# SFP.net
KiCad netlist of a schematic drawn in Altium Designer
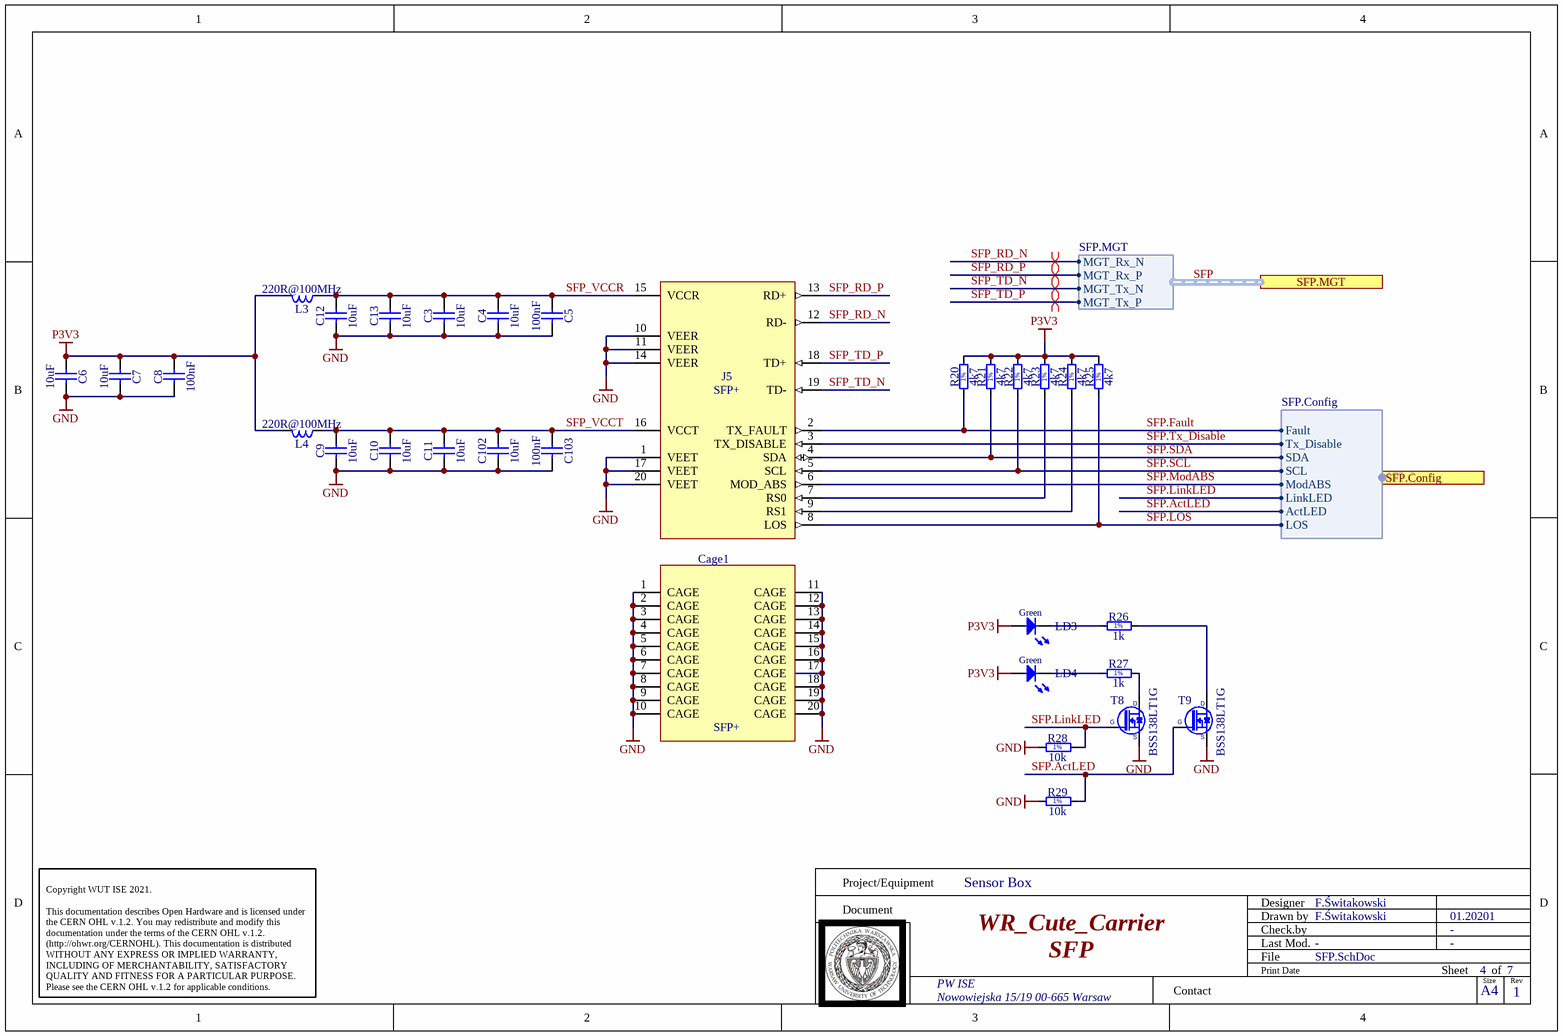
[diagram p0: SFP.SchDoc]

(export (version "E")
  (design (tool "Eeschema 10.0.6"))
  (components
    (comp (ref "C3")
      (value "10uF")
      (footprint "CAPC1005X70N")
      (description "Non-polarised capacitor")
      (fields
        (field (name "PART NUMBER") "CC0402_10UF_6.3V_20%_X5R")
        (field (name "VOLTAGE") "6.3V")
        (field (name "AUTHOR") "CERN DEM JLC")
      )
      (libsource (lib "Capacitors") (part "Capacitor - non polarized"))
    )
    (comp (ref "C4")
      (value "10uF")
      (footprint "CAPC1005X70N")
      (description "Non-polarised capacitor")
      (fields
        (field (name "PART NUMBER") "CC0402_10UF_6.3V_20%_X5R")
        (field (name "VOLTAGE") "6.3V")
        (field (name "AUTHOR") "CERN DEM JLC")
      )
      (libsource (lib "Capacitors") (part "Capacitor - non polarized"))
    )
    (comp (ref "C5")
      (value "100nF")
      (footprint "CAPC1005X55N")
      (description "Non-polarised capacitor")
      (fields
        (field (name "PART NUMBER") "CC0402_100NF_25V_10%_X7R_YUDEN_TMK105B7104KVHF")
        (field (name "VOLTAGE") "25V")
        (field (name "AUTHOR") "CERN DEM JLC")
      )
      (libsource (lib "Capacitors") (part "Capacitor - non polarized"))
    )
    (comp (ref "C6")
      (value "10uF")
      (footprint "CAPC1005X70N")
      (description "Non-polarised capacitor")
      (fields
        (field (name "PART NUMBER") "CC0402_10UF_6.3V_20%_X5R")
        (field (name "VOLTAGE") "6.3V")
        (field (name "AUTHOR") "CERN DEM JLC")
      )
      (libsource (lib "Capacitors") (part "Capacitor - non polarized"))
    )
    (comp (ref "C7")
      (value "10uF")
      (footprint "CAPC1005X70N")
      (description "Non-polarised capacitor")
      (fields
        (field (name "PART NUMBER") "CC0402_10UF_6.3V_20%_X5R")
        (field (name "VOLTAGE") "6.3V")
        (field (name "AUTHOR") "CERN DEM JLC")
      )
      (libsource (lib "Capacitors") (part "Capacitor - non polarized"))
    )
    (comp (ref "C8")
      (value "100nF")
      (footprint "CAPC1005X55N")
      (description "Non-polarised capacitor")
      (fields
        (field (name "PART NUMBER") "CC0402_100NF_25V_10%_X7R_YUDEN_TMK105B7104KVHF")
        (field (name "VOLTAGE") "25V")
        (field (name "AUTHOR") "CERN DEM JLC")
      )
      (libsource (lib "Capacitors") (part "Capacitor - non polarized"))
    )
    (comp (ref "C9")
      (value "10uF")
      (footprint "CAPC1005X70N")
      (description "Non-polarised capacitor")
      (fields
        (field (name "PART NUMBER") "CC0402_10UF_6.3V_20%_X5R")
        (field (name "VOLTAGE") "6.3V")
        (field (name "AUTHOR") "CERN DEM JLC")
      )
      (libsource (lib "Capacitors") (part "Capacitor - non polarized"))
    )
    (comp (ref "C10")
      (value "10uF")
      (footprint "CAPC1005X70N")
      (description "Non-polarised capacitor")
      (fields
        (field (name "PART NUMBER") "CC0402_10UF_6.3V_20%_X5R")
        (field (name "VOLTAGE") "6.3V")
        (field (name "AUTHOR") "CERN DEM JLC")
      )
      (libsource (lib "Capacitors") (part "Capacitor - non polarized"))
    )
    (comp (ref "C11")
      (value "10uF")
      (footprint "CAPC1005X70N")
      (description "Non-polarised capacitor")
      (fields
        (field (name "PART NUMBER") "CC0402_10UF_6.3V_20%_X5R")
        (field (name "VOLTAGE") "6.3V")
        (field (name "AUTHOR") "CERN DEM JLC")
      )
      (libsource (lib "Capacitors") (part "Capacitor - non polarized"))
    )
    (comp (ref "C12")
      (value "10uF")
      (footprint "CAPC1005X70N")
      (description "Non-polarised capacitor")
      (fields
        (field (name "PART NUMBER") "CC0402_10UF_6.3V_20%_X5R")
        (field (name "VOLTAGE") "6.3V")
        (field (name "AUTHOR") "CERN DEM JLC")
      )
      (libsource (lib "Capacitors") (part "Capacitor - non polarized"))
    )
    (comp (ref "C13")
      (value "10uF")
      (footprint "CAPC1005X70N")
      (description "Non-polarised capacitor")
      (fields
        (field (name "PART NUMBER") "CC0402_10UF_6.3V_20%_X5R")
        (field (name "VOLTAGE") "6.3V")
        (field (name "AUTHOR") "CERN DEM JLC")
      )
      (libsource (lib "Capacitors") (part "Capacitor - non polarized"))
    )
    (comp (ref "C102")
      (value "10uF")
      (footprint "CAPC1005X70N")
      (description "Non-polarised capacitor")
      (fields
        (field (name "PART NUMBER") "CC0402_10UF_6.3V_20%_X5R")
        (field (name "VOLTAGE") "6.3V")
        (field (name "AUTHOR") "CERN DEM JLC")
      )
      (libsource (lib "Capacitors") (part "Capacitor - non polarized"))
    )
    (comp (ref "C103")
      (value "100nF")
      (footprint "CAPC1005X55N")
      (description "Non-polarised capacitor")
      (fields
        (field (name "PART NUMBER") "CC0402_100NF_25V_10%_X7R_YUDEN_TMK105B7104KVHF")
        (field (name "VOLTAGE") "25V")
        (field (name "AUTHOR") "CERN DEM JLC")
      )
      (libsource (lib "Capacitors") (part "Capacitor - non polarized"))
    )
    (comp (ref "Cage1")
      (value "SFP+")
      (footprint "TYCO_2007198-1")
      (description "SFP+ 1x1 Cage (20Pins)")
      (fields
        (field (name "PART NUMBER") "TYCO_2007198-1")
        (field (name "MANUFACTURER") "TYCO ELECTRONICS")
        (field (name "AUTHOR") "CERN DEM JLC")
      )
      (libsource (lib "Connectors") (part "SFP+ 1x1 Cage (20Pins)"))
    )
    (comp (ref "J5")
      (value "SFP+")
      (footprint "TYCO_1888247-1")
      (description "20 Position SFP+ Connector (Small Form-factor Pluggable)")
      (fields
        (field (name "PART NUMBER") "TYCO_1888247-1")
        (field (name "MANUFACTURER") "TYCO ELECTRONICS")
        (field (name "AUTHOR") "CERN DEM JLC")
      )
      (libsource (lib "Connectors") (part "SFP+x1"))
    )
    (comp (ref "L3")
      (value "220R@100MHz")
      (footprint "INDC2012X105N")
      (description "Inductor")
      (fields
        (field (name "PART NUMBER") "IND0805_MURATA_BLM21PG221SN1D")
        (field (name "POWER") "2A")
        (field (name "AUTHOR") "CERN DEM JLC")
      )
      (libsource (lib "Inductors & Transformers") (part "Inductor"))
    )
    (comp (ref "L4")
      (value "220R@100MHz")
      (footprint "INDC2012X105N")
      (description "Inductor")
      (fields
        (field (name "PART NUMBER") "IND0805_MURATA_BLM21PG221SN1D")
        (field (name "POWER") "2A")
        (field (name "AUTHOR") "CERN DEM JLC")
      )
      (libsource (lib "Inductors & Transformers") (part "Inductor"))
    )
    (comp (ref "LD3")
      (value "Green")
      (footprint "LED_AVAGO_HSME-C120")
      (description "LED Green 1C 2A")
      (fields
        (field (name "PART NUMBER") "LED_AVAGO_HSME-C120")
        (field (name "MANUFACTURER") "AVAGO TECHNOLOGIES")
        (field (name "AUTHOR") "CERN DEM JMW")
      )
      (libsource (lib "ICs And Semiconductors") (part "LED Green 1C 2A"))
    )
    (comp (ref "LD4")
      (value "Green")
      (footprint "LED_AVAGO_HSME-C120")
      (description "LED Green 1C 2A")
      (fields
        (field (name "PART NUMBER") "LED_AVAGO_HSME-C120")
        (field (name "MANUFACTURER") "AVAGO TECHNOLOGIES")
        (field (name "AUTHOR") "CERN DEM JMW")
      )
      (libsource (lib "ICs And Semiconductors") (part "LED Green 1C 2A"))
    )
    (comp (ref "R20")
      (value "4k7")
      (footprint "RESC1005X40N")
      (description "Resistor - 1%")
      (fields
        (field (name "PART NUMBER") "R0402_4K7_1%_0.0625W_100PPM")
        (field (name "MANUFACTURER") "GENERIC")
        (field (name "AUTHOR") "CERN DEM JLC")
      )
      (libsource (lib "Resistors") (part "Resistor - 1%"))
    )
    (comp (ref "R21")
      (value "4k7")
      (footprint "RESC1005X40N")
      (description "Resistor - 1%")
      (fields
        (field (name "PART NUMBER") "R0402_4K7_1%_0.0625W_100PPM")
        (field (name "MANUFACTURER") "GENERIC")
        (field (name "AUTHOR") "CERN DEM JLC")
      )
      (libsource (lib "Resistors") (part "Resistor - 1%"))
    )
    (comp (ref "R22")
      (value "4k7")
      (footprint "RESC1005X40N")
      (description "Resistor - 1%")
      (fields
        (field (name "PART NUMBER") "R0402_4K7_1%_0.0625W_100PPM")
        (field (name "MANUFACTURER") "GENERIC")
        (field (name "AUTHOR") "CERN DEM JLC")
      )
      (libsource (lib "Resistors") (part "Resistor - 1%"))
    )
    (comp (ref "R23")
      (value "4k7")
      (footprint "RESC1005X40N")
      (description "Resistor - 1%")
      (fields
        (field (name "PART NUMBER") "R0402_4K7_1%_0.0625W_100PPM")
        (field (name "MANUFACTURER") "GENERIC")
        (field (name "AUTHOR") "CERN DEM JLC")
      )
      (libsource (lib "Resistors") (part "Resistor - 1%"))
    )
    (comp (ref "R24")
      (value "4k7")
      (footprint "RESC1005X40N")
      (description "Resistor - 1%")
      (fields
        (field (name "PART NUMBER") "R0402_4K7_1%_0.0625W_100PPM")
        (field (name "MANUFACTURER") "GENERIC")
        (field (name "AUTHOR") "CERN DEM JLC")
      )
      (libsource (lib "Resistors") (part "Resistor - 1%"))
    )
    (comp (ref "R25")
      (value "4k7")
      (footprint "RESC1005X40N")
      (description "Resistor - 1%")
      (fields
        (field (name "PART NUMBER") "R0402_4K7_1%_0.0625W_100PPM")
        (field (name "MANUFACTURER") "GENERIC")
        (field (name "AUTHOR") "CERN DEM JLC")
      )
      (libsource (lib "Resistors") (part "Resistor - 1%"))
    )
    (comp (ref "R26")
      (value "1k")
      (footprint "RESC1005X40N")
      (description "Resistor - 1%")
      (fields
        (field (name "PART NUMBER") "R0402_1K_1%_0.0625W_100PPM")
        (field (name "POWER") "0.0625W")
        (field (name "AUTHOR") "CERN DEM JLC")
      )
      (libsource (lib "Resistors") (part "Resistor - 1%"))
    )
    (comp (ref "R27")
      (value "1k")
      (footprint "RESC1005X40N")
      (description "Resistor - 1%")
      (fields
        (field (name "PART NUMBER") "R0402_1K_1%_0.0625W_100PPM")
        (field (name "POWER") "0.0625W")
        (field (name "AUTHOR") "CERN DEM JLC")
      )
      (libsource (lib "Resistors") (part "Resistor - 1%"))
    )
    (comp (ref "R28")
      (value "10k")
      (footprint "RESC1608X55N")
      (description "Resistor - 1%")
      (fields
        (field (name "PART NUMBER") "R0603_10K_1%_0.1W_100PPM")
        (field (name "POWER") "0.1W")
        (field (name "AUTHOR") "CERN DEM JLC")
      )
      (libsource (lib "Resistors") (part "Resistor - 1%"))
    )
    (comp (ref "R29")
      (value "10k")
      (footprint "RESC1608X55N")
      (description "Resistor - 1%")
      (fields
        (field (name "PART NUMBER") "R0603_10K_1%_0.1W_100PPM")
        (field (name "POWER") "0.1W")
        (field (name "AUTHOR") "CERN DEM JLC")
      )
      (libsource (lib "Resistors") (part "Resistor - 1%"))
    )
    (comp (ref "T8")
      (value "BSS138LT1G")
      (footprint "SOT95P240X110-3N")
      (description "N-CHANNEL MOSFET WITH DIODE")
      (fields (field (name "MANUFACTURER") "ON SEMICONDUCTOR") (field (name "AUTHOR") "CERN DEM JLC"))
      (libsource (lib "ICs And Semiconductors") (part "N-MOSFET-D 1G 2S 3D"))
    )
    (comp (ref "T9")
      (value "BSS138LT1G")
      (footprint "SOT95P240X110-3N")
      (description "N-CHANNEL MOSFET WITH DIODE")
      (fields (field (name "MANUFACTURER") "ON SEMICONDUCTOR") (field (name "AUTHOR") "CERN DEM JLC"))
      (libsource (lib "ICs And Semiconductors") (part "N-MOSFET-D 1G 2S 3D"))
    )
  )
  (nets
    (net (code "3") (name "/SFP.ActLED") (class "Default")
      (node (ref "R29") (pin "2") (pinfunction "2_2") (pintype "passive"))
      (node (ref "T9") (pin "1") (pinfunction "G_1") (pintype "passive"))
    )
    (net (code "4") (name "/SFP.Fault") (class "Default")
      (node (ref "J5") (pin "2") (pinfunction "TX_FAULT_2") (pintype "output"))
      (node (ref "R20") (pin "1") (pinfunction "1_1") (pintype "passive"))
    )
    (net (code "5") (name "/SFP.LOS") (class "Default")
      (node (ref "J5") (pin "8") (pinfunction "LOS_8") (pintype "output"))
      (node (ref "R25") (pin "1") (pinfunction "1_1") (pintype "passive"))
    )
    (net (code "6") (name "/SFP.LinkLED") (class "Default")
      (node (ref "R28") (pin "2") (pinfunction "2_2") (pintype "passive"))
      (node (ref "T8") (pin "1") (pinfunction "G_1") (pintype "passive"))
    )
    (net (code "7") (name "/SFP.ModABS") (class "Default")
      (node (ref "J5") (pin "6") (pinfunction "MOD_ABS_6") (pintype "output"))
    )
    (net (code "8") (name "/SFP.SCL") (class "Default")
      (node (ref "J5") (pin "5") (pinfunction "SCL_5") (pintype "input"))
      (node (ref "R22") (pin "1") (pinfunction "1_1") (pintype "passive"))
    )
    (net (code "9") (name "/SFP.SDA") (class "Default")
      (node (ref "J5") (pin "4") (pinfunction "SDA_4") (pintype "bidirectional"))
      (node (ref "R21") (pin "1") (pinfunction "1_1") (pintype "passive"))
    )
    (net (code "10") (name "/SFP.Tx_Disable") (class "Default")
      (node (ref "J5") (pin "3") (pinfunction "TX_DISABLE_3") (pintype "input"))
    )
    (net (code "11") (name "/SFP_RD_N") (class "Default")
      (node (ref "J5") (pin "12") (pinfunction "RD-_12") (pintype "output"))
    )
    (net (code "12") (name "/SFP_RD_P") (class "Default")
      (node (ref "J5") (pin "13") (pinfunction "RD+_13") (pintype "output"))
    )
    (net (code "13") (name "/SFP_TD_N") (class "Default")
      (node (ref "J5") (pin "19") (pinfunction "TD-_19") (pintype "input"))
    )
    (net (code "14") (name "/SFP_TD_P") (class "Default")
      (node (ref "J5") (pin "18") (pinfunction "TD+_18") (pintype "input"))
    )
    (net (code "15") (name "/SFP_VCCR") (class "Default")
      (node (ref "C12") (pin "2") (pinfunction "2_2") (pintype "passive"))
      (node (ref "C13") (pin "2") (pinfunction "2_2") (pintype "passive"))
      (node (ref "C3") (pin "2") (pinfunction "2_2") (pintype "passive"))
      (node (ref "C4") (pin "2") (pinfunction "2_2") (pintype "passive"))
      (node (ref "C5") (pin "1") (pinfunction "1_1") (pintype "passive"))
      (node (ref "J5") (pin "15") (pinfunction "VCCR_15") (pintype "power_in"))
      (node (ref "L3") (pin "1") (pinfunction "1_1") (pintype "passive"))
    )
    (net (code "16") (name "/SFP_VCCT") (class "Default")
      (node (ref "C10") (pin "2") (pinfunction "2_2") (pintype "passive"))
      (node (ref "C102") (pin "2") (pinfunction "2_2") (pintype "passive"))
      (node (ref "C103") (pin "1") (pinfunction "1_1") (pintype "passive"))
      (node (ref "C11") (pin "2") (pinfunction "2_2") (pintype "passive"))
      (node (ref "C9") (pin "2") (pinfunction "2_2") (pintype "passive"))
      (node (ref "J5") (pin "16") (pinfunction "VCCT_16") (pintype "power_in"))
      (node (ref "L4") (pin "1") (pinfunction "1_1") (pintype "passive"))
    )
    (net (code "19") (name "GND") (class "Default")
      (node (ref "C10") (pin "1") (pinfunction "1_1") (pintype "passive"))
      (node (ref "C102") (pin "1") (pinfunction "1_1") (pintype "passive"))
      (node (ref "C103") (pin "2") (pinfunction "2_2") (pintype "passive"))
      (node (ref "C11") (pin "1") (pinfunction "1_1") (pintype "passive"))
      (node (ref "C12") (pin "1") (pinfunction "1_1") (pintype "passive"))
      (node (ref "C13") (pin "1") (pinfunction "1_1") (pintype "passive"))
      (node (ref "C3") (pin "1") (pinfunction "1_1") (pintype "passive"))
      (node (ref "C4") (pin "1") (pinfunction "1_1") (pintype "passive"))
      (node (ref "C5") (pin "2") (pinfunction "2_2") (pintype "passive"))
      (node (ref "C6") (pin "1") (pinfunction "1_1") (pintype "passive"))
      (node (ref "C7") (pin "1") (pinfunction "1_1") (pintype "passive"))
      (node (ref "C8") (pin "2") (pinfunction "2_2") (pintype "passive"))
      (node (ref "C9") (pin "1") (pinfunction "1_1") (pintype "passive"))
      (node (ref "Cage1") (pin "1") (pinfunction "CAGE_1") (pintype "power_in"))
      (node (ref "Cage1") (pin "10") (pinfunction "CAGE_10") (pintype "power_in"))
      (node (ref "Cage1") (pin "11") (pinfunction "CAGE_11") (pintype "power_in"))
      (node (ref "Cage1") (pin "12") (pinfunction "CAGE_12") (pintype "power_in"))
      (node (ref "Cage1") (pin "13") (pinfunction "CAGE_13") (pintype "power_in"))
      (node (ref "Cage1") (pin "14") (pinfunction "CAGE_14") (pintype "power_in"))
      (node (ref "Cage1") (pin "15") (pinfunction "CAGE_15") (pintype "power_in"))
      (node (ref "Cage1") (pin "16") (pinfunction "CAGE_16") (pintype "power_in"))
      (node (ref "Cage1") (pin "17") (pinfunction "CAGE_17") (pintype "power_in"))
      (node (ref "Cage1") (pin "18") (pinfunction "CAGE_18") (pintype "power_in"))
      (node (ref "Cage1") (pin "19") (pinfunction "CAGE_19") (pintype "power_in"))
      (node (ref "Cage1") (pin "2") (pinfunction "CAGE_2") (pintype "power_in"))
      (node (ref "Cage1") (pin "20") (pinfunction "CAGE_20") (pintype "power_in"))
      (node (ref "Cage1") (pin "3") (pinfunction "CAGE_3") (pintype "power_in"))
      (node (ref "Cage1") (pin "4") (pinfunction "CAGE_4") (pintype "power_in"))
      (node (ref "Cage1") (pin "5") (pinfunction "CAGE_5") (pintype "power_in"))
      (node (ref "Cage1") (pin "6") (pinfunction "CAGE_6") (pintype "power_in"))
      (node (ref "Cage1") (pin "7") (pinfunction "CAGE_7") (pintype "power_in"))
      (node (ref "Cage1") (pin "8") (pinfunction "CAGE_8") (pintype "power_in"))
      (node (ref "Cage1") (pin "9") (pinfunction "CAGE_9") (pintype "power_in"))
      (node (ref "J5") (pin "1") (pinfunction "VEET_1") (pintype "power_in"))
      (node (ref "J5") (pin "10") (pinfunction "VEER_10") (pintype "power_in"))
      (node (ref "J5") (pin "11") (pinfunction "VEER_11") (pintype "power_in"))
      (node (ref "J5") (pin "14") (pinfunction "VEER_14") (pintype "power_in"))
      (node (ref "J5") (pin "17") (pinfunction "VEET_17") (pintype "power_in"))
      (node (ref "J5") (pin "20") (pinfunction "VEET_20") (pintype "power_in"))
      (node (ref "R28") (pin "1") (pinfunction "1_1") (pintype "passive"))
      (node (ref "R29") (pin "1") (pinfunction "1_1") (pintype "passive"))
      (node (ref "T8") (pin "2") (pinfunction "S_2") (pintype "passive"))
      (node (ref "T9") (pin "2") (pinfunction "S_2") (pintype "passive"))
    )
    (net (code "20") (name "Net-(J5-RS0)") (class "Default")
      (node (ref "J5") (pin "7") (pinfunction "RS0_7") (pintype "input"))
      (node (ref "R23") (pin "1") (pinfunction "1_1") (pintype "passive"))
    )
    (net (code "21") (name "Net-(J5-RS1)") (class "Default")
      (node (ref "J5") (pin "9") (pinfunction "RS1_9") (pintype "input"))
      (node (ref "R24") (pin "1") (pinfunction "1_1") (pintype "passive"))
    )
    (net (code "22") (name "Net-(LD3-C)") (class "Default")
      (node (ref "LD3") (pin "1") (pinfunction "C_1") (pintype "passive"))
      (node (ref "R26") (pin "1") (pinfunction "1_1") (pintype "passive"))
    )
    (net (code "23") (name "Net-(LD4-C)") (class "Default")
      (node (ref "LD4") (pin "1") (pinfunction "C_1") (pintype "passive"))
      (node (ref "R27") (pin "1") (pinfunction "1_1") (pintype "passive"))
    )
    (net (code "24") (name "Net-(T8-D)") (class "Default")
      (node (ref "R27") (pin "2") (pinfunction "2_2") (pintype "passive"))
      (node (ref "T8") (pin "3") (pinfunction "D_3") (pintype "passive"))
    )
    (net (code "25") (name "Net-(T9-D)") (class "Default")
      (node (ref "R26") (pin "2") (pinfunction "2_2") (pintype "passive"))
      (node (ref "T9") (pin "3") (pinfunction "D_3") (pintype "passive"))
    )
    (net (code "26") (name "P3V3") (class "Default")
      (node (ref "C6") (pin "2") (pinfunction "2_2") (pintype "passive"))
      (node (ref "C7") (pin "2") (pinfunction "2_2") (pintype "passive"))
      (node (ref "C8") (pin "1") (pinfunction "1_1") (pintype "passive"))
      (node (ref "L3") (pin "2") (pinfunction "2_2") (pintype "passive"))
      (node (ref "L4") (pin "2") (pinfunction "2_2") (pintype "passive"))
      (node (ref "LD3") (pin "2") (pinfunction "A_2") (pintype "passive"))
      (node (ref "LD4") (pin "2") (pinfunction "A_2") (pintype "passive"))
      (node (ref "R20") (pin "2") (pinfunction "2_2") (pintype "passive"))
      (node (ref "R21") (pin "2") (pinfunction "2_2") (pintype "passive"))
      (node (ref "R22") (pin "2") (pinfunction "2_2") (pintype "passive"))
      (node (ref "R23") (pin "2") (pinfunction "2_2") (pintype "passive"))
      (node (ref "R24") (pin "2") (pinfunction "2_2") (pintype "passive"))
      (node (ref "R25") (pin "2") (pinfunction "2_2") (pintype "passive"))
    )
  )
)
